# design.net
KiCad netlist of a schematic drawn in Altium Designer
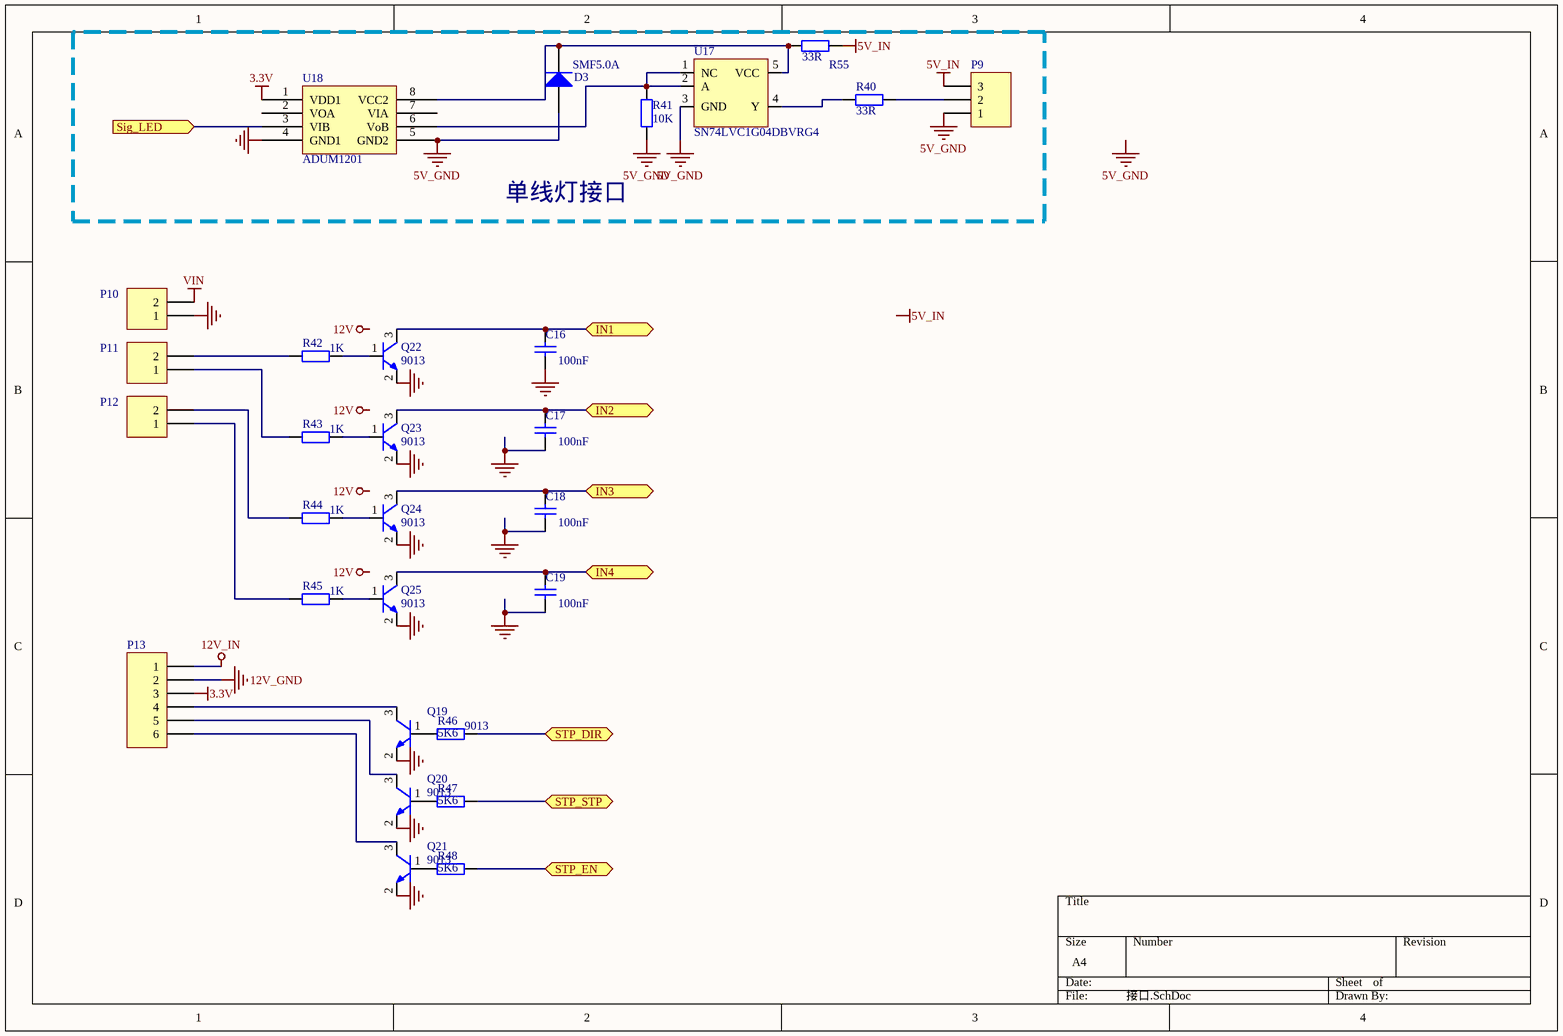
[diagram p0: 接口.SchDoc]

(export (version "E")
  (design (tool "Eeschema 10.0.6"))
  (components
    (comp (ref "C16")
      (value "100nF")
      (footprint "1608C")
      (description "Capacitor")
      (fields (field (name "PUBLISHER") "Altium Limited"))
      (libsource (lib "Miscellaneous Devices") (part "Cap"))
    )
    (comp (ref "C17")
      (value "100nF")
      (footprint "1608C")
      (description "Capacitor")
      (fields (field (name "PUBLISHER") "Altium Limited"))
      (libsource (lib "Miscellaneous Devices") (part "Cap"))
    )
    (comp (ref "C18")
      (value "100nF")
      (footprint "1608C")
      (description "Capacitor")
      (fields (field (name "PUBLISHER") "Altium Limited"))
      (libsource (lib "Miscellaneous Devices") (part "Cap"))
    )
    (comp (ref "C19")
      (value "100nF")
      (footprint "1608C")
      (description "Capacitor")
      (fields (field (name "PUBLISHER") "Altium Limited"))
      (libsource (lib "Miscellaneous Devices") (part "Cap"))
    )
    (comp (ref "D3")
      (value "SMF5.0A")
      (footprint "SOD-123")
      (description "Default Diode")
      (fields (field (name "PUBLISHER") "Altium Limited"))
      (libsource (lib "*") (part "Diode"))
    )
    (comp (ref "P9")
      (value "~")
      (footprint "KF2EDGV-3.81/3")
      (description "Header, 3-Pin")
      (fields (field (name "PUBLISHER") "Altium Limited"))
      (libsource (lib "Miscellaneous Connectors") (part "Header 3"))
    )
    (comp (ref "P10")
      (value "~")
      (footprint "KF128-3.81-2P")
      (description "Header, 2-Pin")
      (fields (field (name "PUBLISHER") "Altium Limited"))
      (libsource (lib "Miscellaneous Connectors") (part "Header 2"))
    )
    (comp (ref "P11")
      (value "~")
      (footprint "KF128-3.81-2P")
      (description "Header, 2-Pin")
      (fields (field (name "PUBLISHER") "Altium Limited"))
      (libsource (lib "Miscellaneous Connectors") (part "Header 2"))
    )
    (comp (ref "P12")
      (value "~")
      (footprint "KF128-3.81-2P")
      (description "Header, 2-Pin")
      (fields (field (name "PUBLISHER") "Altium Limited"))
      (libsource (lib "Miscellaneous Connectors") (part "Header 2"))
    )
    (comp (ref "P13")
      (value "~")
      (footprint "5264-6")
      (description "Header, 6-Pin")
      (fields (field (name "PUBLISHER") "Altium Limited"))
      (libsource (lib "Miscellaneous Connectors") (part "Header 6"))
    )
    (comp (ref "Q19") (value "9013") (footprint "sot-23") (libsource (lib "*") (part "NPNBT")))
    (comp (ref "Q20") (value "9013") (footprint "sot-23") (libsource (lib "*") (part "NPNBT")))
    (comp (ref "Q21") (value "9013") (footprint "sot-23") (libsource (lib "*") (part "NPNBT")))
    (comp (ref "Q22") (value "9013") (footprint "sot-23") (libsource (lib "*") (part "NPNBT")))
    (comp (ref "Q23") (value "9013") (footprint "sot-23") (libsource (lib "*") (part "NPNBT")))
    (comp (ref "Q24") (value "9013") (footprint "sot-23") (libsource (lib "*") (part "NPNBT")))
    (comp (ref "Q25") (value "9013") (footprint "sot-23") (libsource (lib "*") (part "NPNBT")))
    (comp (ref "R40")
      (value "33R")
      (footprint "1608")
      (description "Resistor")
      (fields (field (name "PUBLISHER") "Altium Limited"))
      (libsource (lib "*") (part "Res2"))
    )
    (comp (ref "R41")
      (value "10K")
      (footprint "1608")
      (description "Resistor")
      (fields (field (name "PUBLISHER") "Altium Limited"))
      (libsource (lib "") (part "Res2_1"))
    )
    (comp (ref "R42")
      (value "1K")
      (footprint "1608")
      (description "Resistor")
      (fields (field (name "PUBLISHER") "Altium Limited"))
      (libsource (lib "*") (part "Res2"))
    )
    (comp (ref "R43")
      (value "1K")
      (footprint "1608")
      (description "Resistor")
      (fields (field (name "PUBLISHER") "Altium Limited"))
      (libsource (lib "*") (part "Res2"))
    )
    (comp (ref "R44")
      (value "1K")
      (footprint "1608")
      (description "Resistor")
      (fields (field (name "PUBLISHER") "Altium Limited"))
      (libsource (lib "*") (part "Res2"))
    )
    (comp (ref "R45")
      (value "1K")
      (footprint "1608")
      (description "Resistor")
      (fields (field (name "PUBLISHER") "Altium Limited"))
      (libsource (lib "*") (part "Res2"))
    )
    (comp (ref "R46")
      (value "5K6")
      (footprint "1608")
      (description "Resistor")
      (fields (field (name "PUBLISHER") "Altium Limited"))
      (libsource (lib "*") (part "Res2"))
    )
    (comp (ref "R47")
      (value "5K6")
      (footprint "1608")
      (description "Resistor")
      (fields (field (name "PUBLISHER") "Altium Limited"))
      (libsource (lib "*") (part "Res2"))
    )
    (comp (ref "R48")
      (value "5K6")
      (footprint "1608")
      (description "Resistor")
      (fields (field (name "PUBLISHER") "Altium Limited"))
      (libsource (lib "*") (part "Res2"))
    )
    (comp (ref "R55")
      (value "33R")
      (footprint "1608")
      (description "Resistor")
      (fields (field (name "PUBLISHER") "Altium Limited"))
      (libsource (lib "*") (part "Res2"))
    )
    (comp (ref "U17")
      (value "SN74LVC1G04DBVRG4")
      (footprint "SOT-23-5")
      (libsource (lib "Schlib1") (part "LMV321"))
    )
    (comp (ref "U18") (value "ADUM1201") (footprint "so8") (libsource (lib "*") (part "max485")))
  )
  (nets
    (net (code "1") (name "/IN1") (class "Default")
      (node (ref "C16") (pin "2") (pinfunction "2_2") (pintype "passive"))
      (node (ref "Q22") (pin "3") (pinfunction "C_3") (pintype "passive"))
    )
    (net (code "2") (name "/IN2") (class "Default")
      (node (ref "C17") (pin "2") (pinfunction "2_2") (pintype "passive"))
      (node (ref "Q23") (pin "3") (pinfunction "C_3") (pintype "passive"))
    )
    (net (code "3") (name "/IN3") (class "Default")
      (node (ref "C18") (pin "2") (pinfunction "2_2") (pintype "passive"))
      (node (ref "Q24") (pin "3") (pinfunction "C_3") (pintype "passive"))
    )
    (net (code "4") (name "/IN4") (class "Default")
      (node (ref "C19") (pin "2") (pinfunction "2_2") (pintype "passive"))
      (node (ref "Q25") (pin "3") (pinfunction "C_3") (pintype "passive"))
    )
    (net (code "5") (name "/STP_DIR") (class "Default")
      (node (ref "R46") (pin "1") (pinfunction "1_1") (pintype "passive"))
    )
    (net (code "6") (name "/STP_EN") (class "Default")
      (node (ref "R48") (pin "1") (pinfunction "1_1") (pintype "passive"))
    )
    (net (code "7") (name "/STP_STP") (class "Default")
      (node (ref "R47") (pin "1") (pinfunction "1_1") (pintype "passive"))
    )
    (net (code "8") (name "/Sig_LED") (class "Default")
      (node (ref "U18") (pin "3") (pinfunction "VIB_3") (pintype "passive"))
    )
    (net (code "9") (name "3.3V") (class "Default")
      (node (ref "P13") (pin "3") (pinfunction "3_3") (pintype "passive"))
      (node (ref "U18") (pin "1") (pinfunction "VDD1_1") (pintype "passive"))
    )
    (net (code "10") (name "5V_GND") (class "Default")
      (node (ref "D3") (pin "1") (pinfunction "A_1") (pintype "passive"))
      (node (ref "P9") (pin "1") (pinfunction "1_1") (pintype "passive"))
      (node (ref "R41") (pin "1") (pinfunction "1_1") (pintype "passive"))
      (node (ref "U17") (pin "3") (pinfunction "GND_3") (pintype "passive"))
      (node (ref "U18") (pin "5") (pinfunction "GND2_5") (pintype "passive"))
    )
    (net (code "11") (name "5V_IN") (class "Default")
      (node (ref "P9") (pin "3") (pinfunction "3_3") (pintype "passive"))
      (node (ref "R55") (pin "1") (pinfunction "1_1") (pintype "passive"))
    )
    (net (code "13") (name "12V_GND") (class "Default")
      (node (ref "P13") (pin "2") (pinfunction "2_2") (pintype "passive"))
    )
    (net (code "14") (name "12V_IN") (class "Default")
      (node (ref "P13") (pin "1") (pinfunction "1_1") (pintype "passive"))
    )
    (net (code "15") (name "GND") (class "Default")
      (node (ref "C16") (pin "1") (pinfunction "1_1") (pintype "passive"))
      (node (ref "C17") (pin "1") (pinfunction "1_1") (pintype "passive"))
      (node (ref "C18") (pin "1") (pinfunction "1_1") (pintype "passive"))
      (node (ref "C19") (pin "1") (pinfunction "1_1") (pintype "passive"))
      (node (ref "P10") (pin "1") (pinfunction "1_1") (pintype "passive"))
      (node (ref "Q19") (pin "2") (pinfunction "E_2") (pintype "passive"))
      (node (ref "Q20") (pin "2") (pinfunction "E_2") (pintype "passive"))
      (node (ref "Q21") (pin "2") (pinfunction "E_2") (pintype "passive"))
      (node (ref "Q22") (pin "2") (pinfunction "E_2") (pintype "passive"))
      (node (ref "Q23") (pin "2") (pinfunction "E_2") (pintype "passive"))
      (node (ref "Q24") (pin "2") (pinfunction "E_2") (pintype "passive"))
      (node (ref "Q25") (pin "2") (pinfunction "E_2") (pintype "passive"))
      (node (ref "U18") (pin "4") (pinfunction "GND1_4") (pintype "passive"))
    )
    (net (code "16") (name "Net-(D3-K)") (class "Default")
      (node (ref "D3") (pin "2") (pinfunction "K_2") (pintype "passive"))
      (node (ref "R55") (pin "2") (pinfunction "2_2") (pintype "passive"))
      (node (ref "U17") (pin "5") (pinfunction "VCC_5") (pintype "passive"))
      (node (ref "U18") (pin "8") (pinfunction "VCC2_8") (pintype "passive"))
    )
    (net (code "17") (name "Net-(P9-Pad2)") (class "Default")
      (node (ref "P9") (pin "2") (pinfunction "2_2") (pintype "passive"))
      (node (ref "R40") (pin "1") (pinfunction "1_1") (pintype "passive"))
    )
    (net (code "18") (name "Net-(P11-Pad1)") (class "Default")
      (node (ref "P11") (pin "1") (pinfunction "1_1") (pintype "passive"))
      (node (ref "R43") (pin "2") (pinfunction "2_2") (pintype "passive"))
    )
    (net (code "19") (name "Net-(P11-Pad2)") (class "Default")
      (node (ref "P11") (pin "2") (pinfunction "2_2") (pintype "passive"))
      (node (ref "R42") (pin "2") (pinfunction "2_2") (pintype "passive"))
    )
    (net (code "20") (name "Net-(P12-Pad1)") (class "Default")
      (node (ref "P12") (pin "1") (pinfunction "1_1") (pintype "passive"))
      (node (ref "R45") (pin "2") (pinfunction "2_2") (pintype "passive"))
    )
    (net (code "21") (name "Net-(P12-Pad2)") (class "Default")
      (node (ref "P12") (pin "2") (pinfunction "2_2") (pintype "passive"))
      (node (ref "R44") (pin "2") (pinfunction "2_2") (pintype "passive"))
    )
    (net (code "22") (name "Net-(Q19-B)") (class "Default")
      (node (ref "Q19") (pin "1") (pinfunction "B_1") (pintype "passive"))
      (node (ref "R46") (pin "2") (pinfunction "2_2") (pintype "passive"))
    )
    (net (code "23") (name "Net-(Q19-C)") (class "Default")
      (node (ref "P13") (pin "4") (pinfunction "4_4") (pintype "passive"))
      (node (ref "Q19") (pin "3") (pinfunction "C_3") (pintype "passive"))
    )
    (net (code "24") (name "Net-(Q20-B)") (class "Default")
      (node (ref "Q20") (pin "1") (pinfunction "B_1") (pintype "passive"))
      (node (ref "R47") (pin "2") (pinfunction "2_2") (pintype "passive"))
    )
    (net (code "25") (name "Net-(Q20-C)") (class "Default")
      (node (ref "P13") (pin "5") (pinfunction "5_5") (pintype "passive"))
      (node (ref "Q20") (pin "3") (pinfunction "C_3") (pintype "passive"))
    )
    (net (code "26") (name "Net-(Q21-B)") (class "Default")
      (node (ref "Q21") (pin "1") (pinfunction "B_1") (pintype "passive"))
      (node (ref "R48") (pin "2") (pinfunction "2_2") (pintype "passive"))
    )
    (net (code "27") (name "Net-(Q21-C)") (class "Default")
      (node (ref "P13") (pin "6") (pinfunction "6_6") (pintype "passive"))
      (node (ref "Q21") (pin "3") (pinfunction "C_3") (pintype "passive"))
    )
    (net (code "28") (name "Net-(Q22-B)") (class "Default")
      (node (ref "Q22") (pin "1") (pinfunction "B_1") (pintype "passive"))
      (node (ref "R42") (pin "1") (pinfunction "1_1") (pintype "passive"))
    )
    (net (code "29") (name "Net-(Q23-B)") (class "Default")
      (node (ref "Q23") (pin "1") (pinfunction "B_1") (pintype "passive"))
      (node (ref "R43") (pin "1") (pinfunction "1_1") (pintype "passive"))
    )
    (net (code "30") (name "Net-(Q24-B)") (class "Default")
      (node (ref "Q24") (pin "1") (pinfunction "B_1") (pintype "passive"))
      (node (ref "R44") (pin "1") (pinfunction "1_1") (pintype "passive"))
    )
    (net (code "31") (name "Net-(Q25-B)") (class "Default")
      (node (ref "Q25") (pin "1") (pinfunction "B_1") (pintype "passive"))
      (node (ref "R45") (pin "1") (pinfunction "1_1") (pintype "passive"))
    )
    (net (code "32") (name "Net-(U17-A)") (class "Default")
      (node (ref "R41") (pin "2") (pinfunction "2_2") (pintype "passive"))
      (node (ref "U17") (pin "1") (pinfunction "NC_1") (pintype "passive"))
      (node (ref "U17") (pin "2") (pinfunction "A_2") (pintype "passive"))
      (node (ref "U18") (pin "6") (pinfunction "VoB_6") (pintype "passive"))
    )
    (net (code "33") (name "Net-(U17-Y)") (class "Default")
      (node (ref "R40") (pin "2") (pinfunction "2_2") (pintype "passive"))
      (node (ref "U17") (pin "4") (pinfunction "Y_4") (pintype "passive"))
    )
    (net (code "34") (name "VIN") (class "Default")
      (node (ref "P10") (pin "2") (pinfunction "2_2") (pintype "passive"))
    )
    (net (code "35") (name "unconnected-(U18-VIA-Pad7)") (class "Default")
      (node (ref "U18") (pin "7") (pinfunction "VIA_7") (pintype "passive"))
    )
    (net (code "36") (name "unconnected-(U18-VOA-Pad2)") (class "Default")
      (node (ref "U18") (pin "2") (pinfunction "VOA_2") (pintype "passive"))
    )
  )
)
